# Pure_VCA.net
KiCad netlist of a schematic drawn in EAGLE
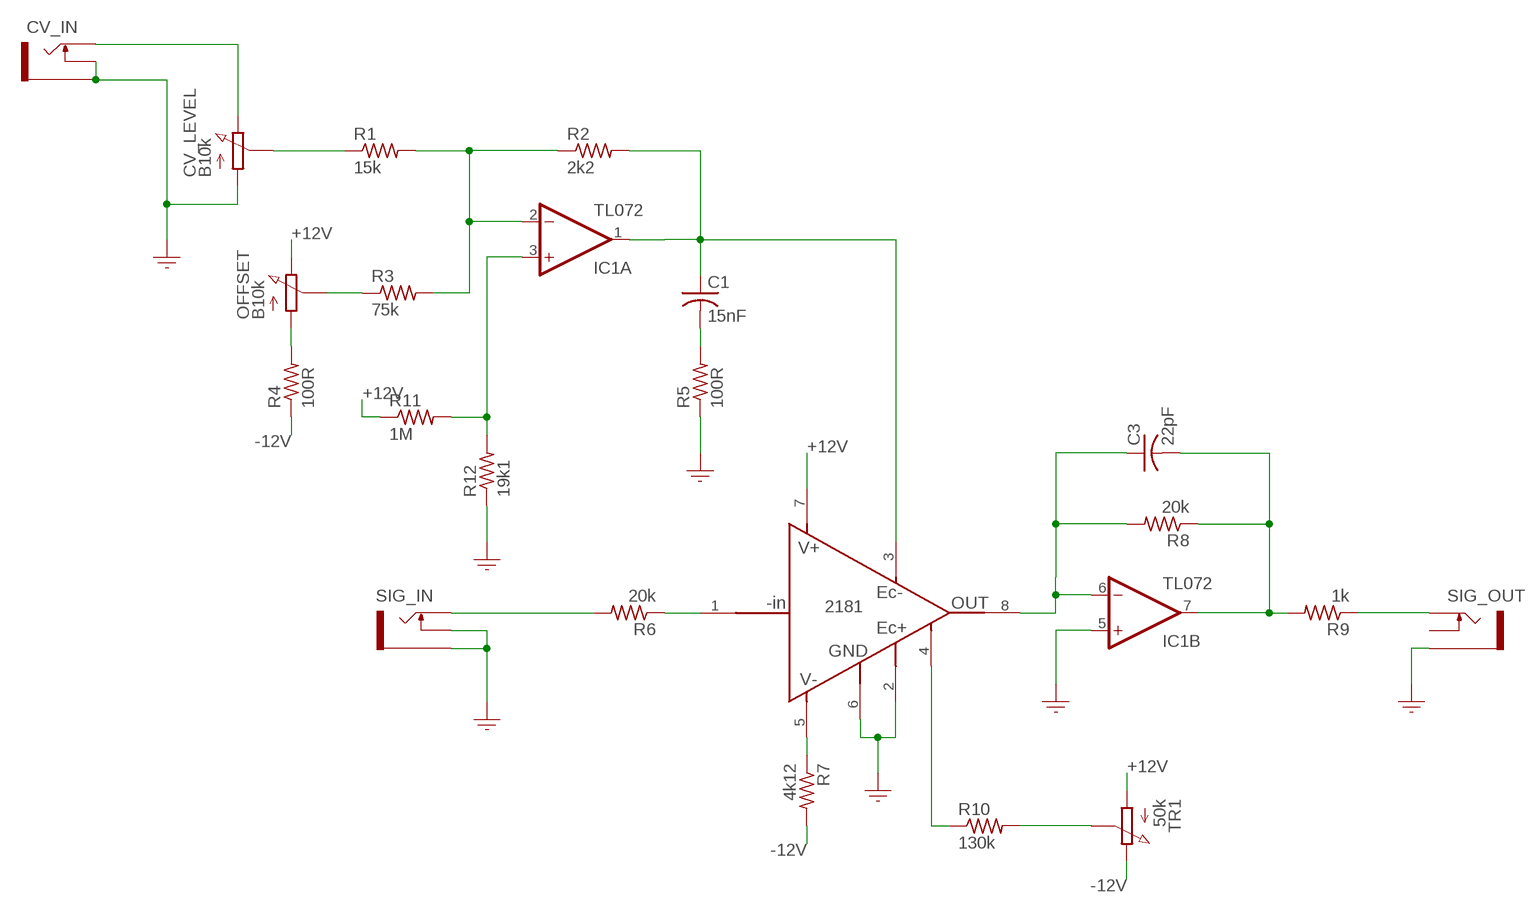
[diagram p0: schematic, sheet 1]
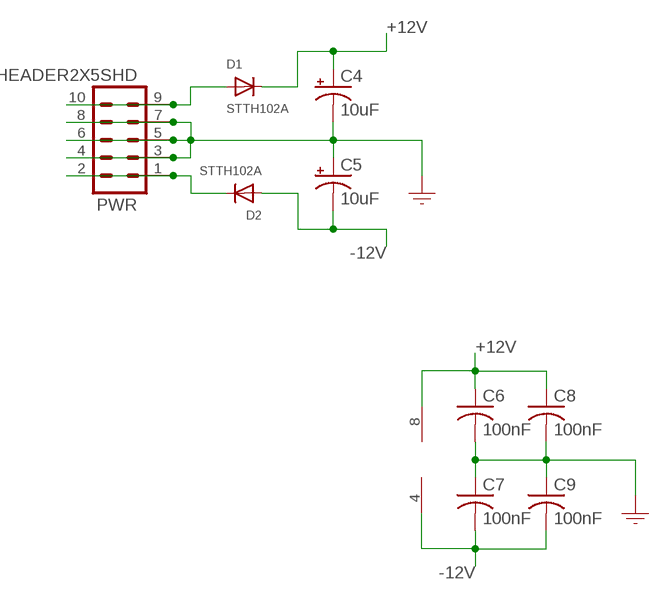
[diagram p1: schematic, sheet 2]

(export (version "E")
  (design (tool "Eeschema 10.0.6"))
  (components
    (comp (ref "C1")
      (value "15nF")
      (footprint "eagle-import:C0805")
      (libsource (lib "eagle-import") (part "CAPACITOR-USC0805"))
    )
    (comp (ref "C3")
      (value "22pF")
      (footprint "eagle-import:C0805")
      (libsource (lib "eagle-import") (part "CAPACITOR-USC0805"))
    )
    (comp (ref "CV_IN")
      (value "PJ301M-12")
      (footprint "eagle-import:PJ301M-12")
      (libsource (lib "eagle-import") (part "SOCKET_MONO_3.5MMPJ301M-12"))
    )
    (comp (ref "CV_LEVEL")
      (value "B10k")
      (footprint "eagle-import:POT_9MM_GREEN_KNOB")
      (libsource (lib "eagle-import") (part "RESISTOR_VARIABLEPOT_9MM_GREEN_KNOB"))
    )
    (comp (ref "IC1")
      (value "TL072")
      (footprint "eagle-import:SO08")
      (libsource (lib "eagle-import") (part "OPAMP_DUALD"))
    )
    (comp (ref "IC2")
      (value "THAT2181")
      (footprint "eagle-import:SOIC--8")
      (libsource (lib "eagle-import") (part "VCA_THAT2181"))
    )
    (comp (ref "OFFSET")
      (value "B10k")
      (footprint "eagle-import:POT_9MM_BLUE_KNOB")
      (libsource (lib "eagle-import") (part "RESISTOR_VARIABLEPOT_9MM_BLUE_KNOB"))
    )
    (comp (ref "R1")
      (value "15k")
      (footprint "eagle-import:R0805")
      (libsource (lib "eagle-import") (part "RESISTOR_USR0805"))
    )
    (comp (ref "R2")
      (value "2k2")
      (footprint "eagle-import:R0805")
      (libsource (lib "eagle-import") (part "RESISTOR_USR0805"))
    )
    (comp (ref "R3")
      (value "75k")
      (footprint "eagle-import:R0805")
      (libsource (lib "eagle-import") (part "RESISTOR_USR0805"))
    )
    (comp (ref "R4")
      (value "100R")
      (footprint "eagle-import:R0805")
      (libsource (lib "eagle-import") (part "RESISTOR_USR0805"))
    )
    (comp (ref "R5")
      (value "100R")
      (footprint "eagle-import:R0805")
      (libsource (lib "eagle-import") (part "RESISTOR_USR0805"))
    )
    (comp (ref "R6")
      (value "20k")
      (footprint "eagle-import:R0805")
      (libsource (lib "eagle-import") (part "RESISTOR_USR0805"))
    )
    (comp (ref "R7")
      (value "4k12")
      (footprint "eagle-import:R0805")
      (libsource (lib "eagle-import") (part "RESISTOR_USR0805"))
    )
    (comp (ref "R8")
      (value "20k")
      (footprint "eagle-import:R0805")
      (libsource (lib "eagle-import") (part "RESISTOR_USR0805"))
    )
    (comp (ref "R9")
      (value "1k")
      (footprint "eagle-import:R0805")
      (libsource (lib "eagle-import") (part "RESISTOR_USR0805"))
    )
    (comp (ref "R10")
      (value "130k")
      (footprint "eagle-import:R0805")
      (libsource (lib "eagle-import") (part "RESISTOR_USR0805"))
    )
    (comp (ref "R11")
      (value "1M")
      (footprint "eagle-import:R0805")
      (libsource (lib "eagle-import") (part "RESISTOR_USR0805"))
    )
    (comp (ref "R12")
      (value "19k1")
      (footprint "eagle-import:R0805")
      (libsource (lib "eagle-import") (part "RESISTOR_USR0805"))
    )
    (comp (ref "SIG_IN")
      (value "PJ301M-12")
      (footprint "eagle-import:PJ301M-12")
      (libsource (lib "eagle-import") (part "SOCKET_MONO_3.5MMPJ301M-12"))
    )
    (comp (ref "SIG_OUT")
      (value "PJ301M-12")
      (footprint "eagle-import:PJ301M-12")
      (libsource (lib "eagle-import") (part "SOCKET_MONO_3.5MMPJ301M-12"))
    )
    (comp (ref "TR1")
      (value "50k")
      (footprint "eagle-import:TRIMMER_TH")
      (libsource (lib "eagle-import") (part "RESISTOR_VARIABLETRIMMER_TH"))
    )
    (comp (ref "C4")
      (value "10uF")
      (footprint "eagle-import:153CLV-0505")
      (libsource (lib "eagle-import") (part "CAPACITOR_POL-US153CLV-0505"))
    )
    (comp (ref "C5")
      (value "10uF")
      (footprint "eagle-import:153CLV-0505")
      (libsource (lib "eagle-import") (part "CAPACITOR_POL-US153CLV-0505"))
    )
    (comp (ref "C6")
      (value "100nF")
      (footprint "eagle-import:C0805")
      (libsource (lib "eagle-import") (part "CAPACITOR-USC0805"))
    )
    (comp (ref "C7")
      (value "100nF")
      (footprint "eagle-import:C0805")
      (libsource (lib "eagle-import") (part "CAPACITOR-USC0805"))
    )
    (comp (ref "C8")
      (value "100nF")
      (footprint "eagle-import:C0805")
      (libsource (lib "eagle-import") (part "CAPACITOR-USC0805"))
    )
    (comp (ref "C9")
      (value "100nF")
      (footprint "eagle-import:C0805")
      (libsource (lib "eagle-import") (part "CAPACITOR-USC0805"))
    )
    (comp (ref "D1")
      (value "STTH102A")
      (footprint "eagle-import:SMADIODE")
      (libsource (lib "eagle-import") (part "DIODESMA"))
    )
    (comp (ref "D2")
      (value "STTH102A")
      (footprint "eagle-import:SMADIODE")
      (libsource (lib "eagle-import") (part "DIODESMA"))
    )
    (comp (ref "PWR")
      (value "HEADER2X5SHD")
      (footprint "eagle-import:2X5-SHROUDED")
      (libsource (lib "eagle-import") (part "HEADER2X5SHD"))
    )
  )
  (nets
    (net (code "1") (name "+12V") (class "Default")
      (node (ref "C4") (pin "+") (pinfunction "+_+") (pintype "passive"))
      (node (ref "C6") (pin "1") (pinfunction "1_1") (pintype "passive"))
      (node (ref "C8") (pin "1") (pinfunction "1_1") (pintype "passive"))
      (node (ref "D1") (pin "C") (pinfunction "C_C") (pintype "passive"))
      (node (ref "IC1") (pin "8") (pinfunction "V+_8") (pintype "power_in"))
      (node (ref "IC2") (pin "7") (pinfunction "V+_7") (pintype "bidirectional"))
      (node (ref "OFFSET") (pin "P$3") (pinfunction "3_P$3") (pintype "passive"))
      (node (ref "R11") (pin "1") (pinfunction "1_1") (pintype "passive"))
      (node (ref "TR1") (pin "1") (pinfunction "1_1") (pintype "passive"))
    )
    (net (code "2") (name "-12V") (class "Default")
      (node (ref "C5") (pin "-") (pinfunction "-_-") (pintype "passive"))
      (node (ref "C7") (pin "2") (pinfunction "2_2") (pintype "passive"))
      (node (ref "C9") (pin "2") (pinfunction "2_2") (pintype "passive"))
      (node (ref "D2") (pin "A") (pinfunction "A_A") (pintype "passive"))
      (node (ref "IC1") (pin "4") (pinfunction "V-_4") (pintype "power_in"))
      (node (ref "R4") (pin "1") (pinfunction "1_1") (pintype "passive"))
      (node (ref "R7") (pin "2") (pinfunction "2_2") (pintype "passive"))
      (node (ref "TR1") (pin "3") (pinfunction "3_3") (pintype "passive"))
    )
    (net (code "3") (name "GND") (class "Default")
      (node (ref "C4") (pin "-") (pinfunction "-_-") (pintype "passive"))
      (node (ref "C5") (pin "+") (pinfunction "+_+") (pintype "passive"))
      (node (ref "C6") (pin "2") (pinfunction "2_2") (pintype "passive"))
      (node (ref "C7") (pin "1") (pinfunction "1_1") (pintype "passive"))
      (node (ref "C8") (pin "2") (pinfunction "2_2") (pintype "passive"))
      (node (ref "C9") (pin "1") (pinfunction "1_1") (pintype "passive"))
      (node (ref "CV_IN") (pin "GND") (pinfunction "SLEEVE_GND") (pintype "passive"))
      (node (ref "CV_IN") (pin "NORM") (pinfunction "SWITCH_NORM") (pintype "passive"))
      (node (ref "CV_LEVEL") (pin "P$1") (pinfunction "1_P$1") (pintype "passive"))
      (node (ref "IC1") (pin "5") (pinfunction "+IN_5") (pintype "input"))
      (node (ref "IC2") (pin "2") (pinfunction "EC+_2") (pintype "bidirectional"))
      (node (ref "IC2") (pin "6") (pinfunction "GND_6") (pintype "bidirectional"))
      (node (ref "PWR") (pin "3") (pinfunction "3_3") (pintype "passive"))
      (node (ref "PWR") (pin "4") (pinfunction "4_4") (pintype "passive"))
      (node (ref "PWR") (pin "5") (pinfunction "5_5") (pintype "passive"))
      (node (ref "PWR") (pin "6") (pinfunction "6_6") (pintype "passive"))
      (node (ref "PWR") (pin "7") (pinfunction "7_7") (pintype "passive"))
      (node (ref "PWR") (pin "8") (pinfunction "8_8") (pintype "passive"))
      (node (ref "R12") (pin "1") (pinfunction "1_1") (pintype "passive"))
      (node (ref "R5") (pin "1") (pinfunction "1_1") (pintype "passive"))
      (node (ref "SIG_IN") (pin "GND") (pinfunction "SLEEVE_GND") (pintype "passive"))
      (node (ref "SIG_IN") (pin "NORM") (pinfunction "SWITCH_NORM") (pintype "passive"))
      (node (ref "SIG_OUT") (pin "GND") (pinfunction "SLEEVE_GND") (pintype "passive"))
    )
    (net (code "4") (name "Net-(C1-Pad2)") (class "Default")
      (node (ref "C1") (pin "2") (pinfunction "2_2") (pintype "passive"))
      (node (ref "R5") (pin "2") (pinfunction "2_2") (pintype "passive"))
    )
    (net (code "5") (name "Net-(CV_LEVEL-2)") (class "Default")
      (node (ref "CV_LEVEL") (pin "P$2") (pinfunction "2_P$2") (pintype "passive"))
      (node (ref "R1") (pin "1") (pinfunction "1_1") (pintype "passive"))
    )
    (net (code "6") (name "Net-(CV_LEVEL-3)") (class "Default")
      (node (ref "CV_IN") (pin "TIP") (pinfunction "TIP_TIP") (pintype "passive"))
      (node (ref "CV_LEVEL") (pin "P$3") (pinfunction "3_P$3") (pintype "passive"))
    )
    (net (code "7") (name "Net-(D1-PadA)") (class "Default")
      (node (ref "D1") (pin "A") (pinfunction "A_A") (pintype "passive"))
      (node (ref "PWR") (pin "10") (pinfunction "10_10") (pintype "passive"))
      (node (ref "PWR") (pin "9") (pinfunction "9_9") (pintype "passive"))
    )
    (net (code "8") (name "Net-(D2-PadC)") (class "Default")
      (node (ref "D2") (pin "C") (pinfunction "C_C") (pintype "passive"))
      (node (ref "PWR") (pin "1") (pinfunction "1_1") (pintype "passive"))
      (node (ref "PWR") (pin "2") (pinfunction "2_2") (pintype "passive"))
    )
    (net (code "9") (name "Net-(IC1A-+IN)") (class "Default")
      (node (ref "IC1") (pin "3") (pinfunction "+IN_3") (pintype "input"))
      (node (ref "R11") (pin "2") (pinfunction "2_2") (pintype "passive"))
      (node (ref "R12") (pin "2") (pinfunction "2_2") (pintype "passive"))
    )
    (net (code "10") (name "Net-(IC1A--IN)") (class "Default")
      (node (ref "IC1") (pin "2") (pinfunction "-IN_2") (pintype "input"))
      (node (ref "R1") (pin "2") (pinfunction "2_2") (pintype "passive"))
      (node (ref "R2") (pin "1") (pinfunction "1_1") (pintype "passive"))
      (node (ref "R3") (pin "2") (pinfunction "2_2") (pintype "passive"))
    )
    (net (code "11") (name "Net-(IC1A-OUT)") (class "Default")
      (node (ref "C1") (pin "1") (pinfunction "1_1") (pintype "passive"))
      (node (ref "IC1") (pin "1") (pinfunction "OUT_1") (pintype "output"))
      (node (ref "IC2") (pin "3") (pinfunction "EC-_3") (pintype "bidirectional"))
      (node (ref "R2") (pin "2") (pinfunction "2_2") (pintype "passive"))
    )
    (net (code "12") (name "Net-(IC1B--IN)") (class "Default")
      (node (ref "C3") (pin "1") (pinfunction "1_1") (pintype "passive"))
      (node (ref "IC1") (pin "6") (pinfunction "-IN_6") (pintype "input"))
      (node (ref "IC2") (pin "8") (pinfunction "OUT_8") (pintype "bidirectional"))
      (node (ref "R8") (pin "2") (pinfunction "2_2") (pintype "passive"))
    )
    (net (code "13") (name "Net-(IC1B-OUT)") (class "Default")
      (node (ref "C3") (pin "2") (pinfunction "2_2") (pintype "passive"))
      (node (ref "IC1") (pin "7") (pinfunction "OUT_7") (pintype "output"))
      (node (ref "R8") (pin "1") (pinfunction "1_1") (pintype "passive"))
      (node (ref "R9") (pin "2") (pinfunction "2_2") (pintype "passive"))
    )
    (net (code "14") (name "Net-(IC2--IN)") (class "Default")
      (node (ref "IC2") (pin "1") (pinfunction "-IN_1") (pintype "bidirectional"))
      (node (ref "R6") (pin "1") (pinfunction "1_1") (pintype "passive"))
    )
    (net (code "15") (name "Net-(IC2-SYM)") (class "Default")
      (node (ref "IC2") (pin "4") (pinfunction "SYM_4") (pintype "bidirectional"))
      (node (ref "R10") (pin "1") (pinfunction "1_1") (pintype "passive"))
    )
    (net (code "16") (name "Net-(IC2-V-)") (class "Default")
      (node (ref "IC2") (pin "5") (pinfunction "V-_5") (pintype "bidirectional"))
      (node (ref "R7") (pin "1") (pinfunction "1_1") (pintype "passive"))
    )
    (net (code "17") (name "Net-(OFFSET-1)") (class "Default")
      (node (ref "OFFSET") (pin "P$1") (pinfunction "1_P$1") (pintype "passive"))
      (node (ref "R4") (pin "2") (pinfunction "2_2") (pintype "passive"))
    )
    (net (code "18") (name "Net-(OFFSET-2)") (class "Default")
      (node (ref "OFFSET") (pin "P$2") (pinfunction "2_P$2") (pintype "passive"))
      (node (ref "R3") (pin "1") (pinfunction "1_1") (pintype "passive"))
    )
    (net (code "19") (name "Net-(R6-Pad2)") (class "Default")
      (node (ref "R6") (pin "2") (pinfunction "2_2") (pintype "passive"))
      (node (ref "SIG_IN") (pin "TIP") (pinfunction "TIP_TIP") (pintype "passive"))
    )
    (net (code "20") (name "Net-(R9-Pad1)") (class "Default")
      (node (ref "R9") (pin "1") (pinfunction "1_1") (pintype "passive"))
      (node (ref "SIG_OUT") (pin "TIP") (pinfunction "TIP_TIP") (pintype "passive"))
    )
    (net (code "21") (name "Net-(R10-Pad2)") (class "Default")
      (node (ref "R10") (pin "2") (pinfunction "2_2") (pintype "passive"))
      (node (ref "TR1") (pin "2") (pinfunction "2_2") (pintype "passive"))
    )
    (net (code "22") (name "unconnected-(SIG_OUT-SWITCH-PadNORM)") (class "Default")
      (node (ref "SIG_OUT") (pin "NORM") (pinfunction "SWITCH_NORM") (pintype "passive"))
    )
  )
)
